# humidity_revc.net
KiCad netlist of a schematic drawn in EAGLE
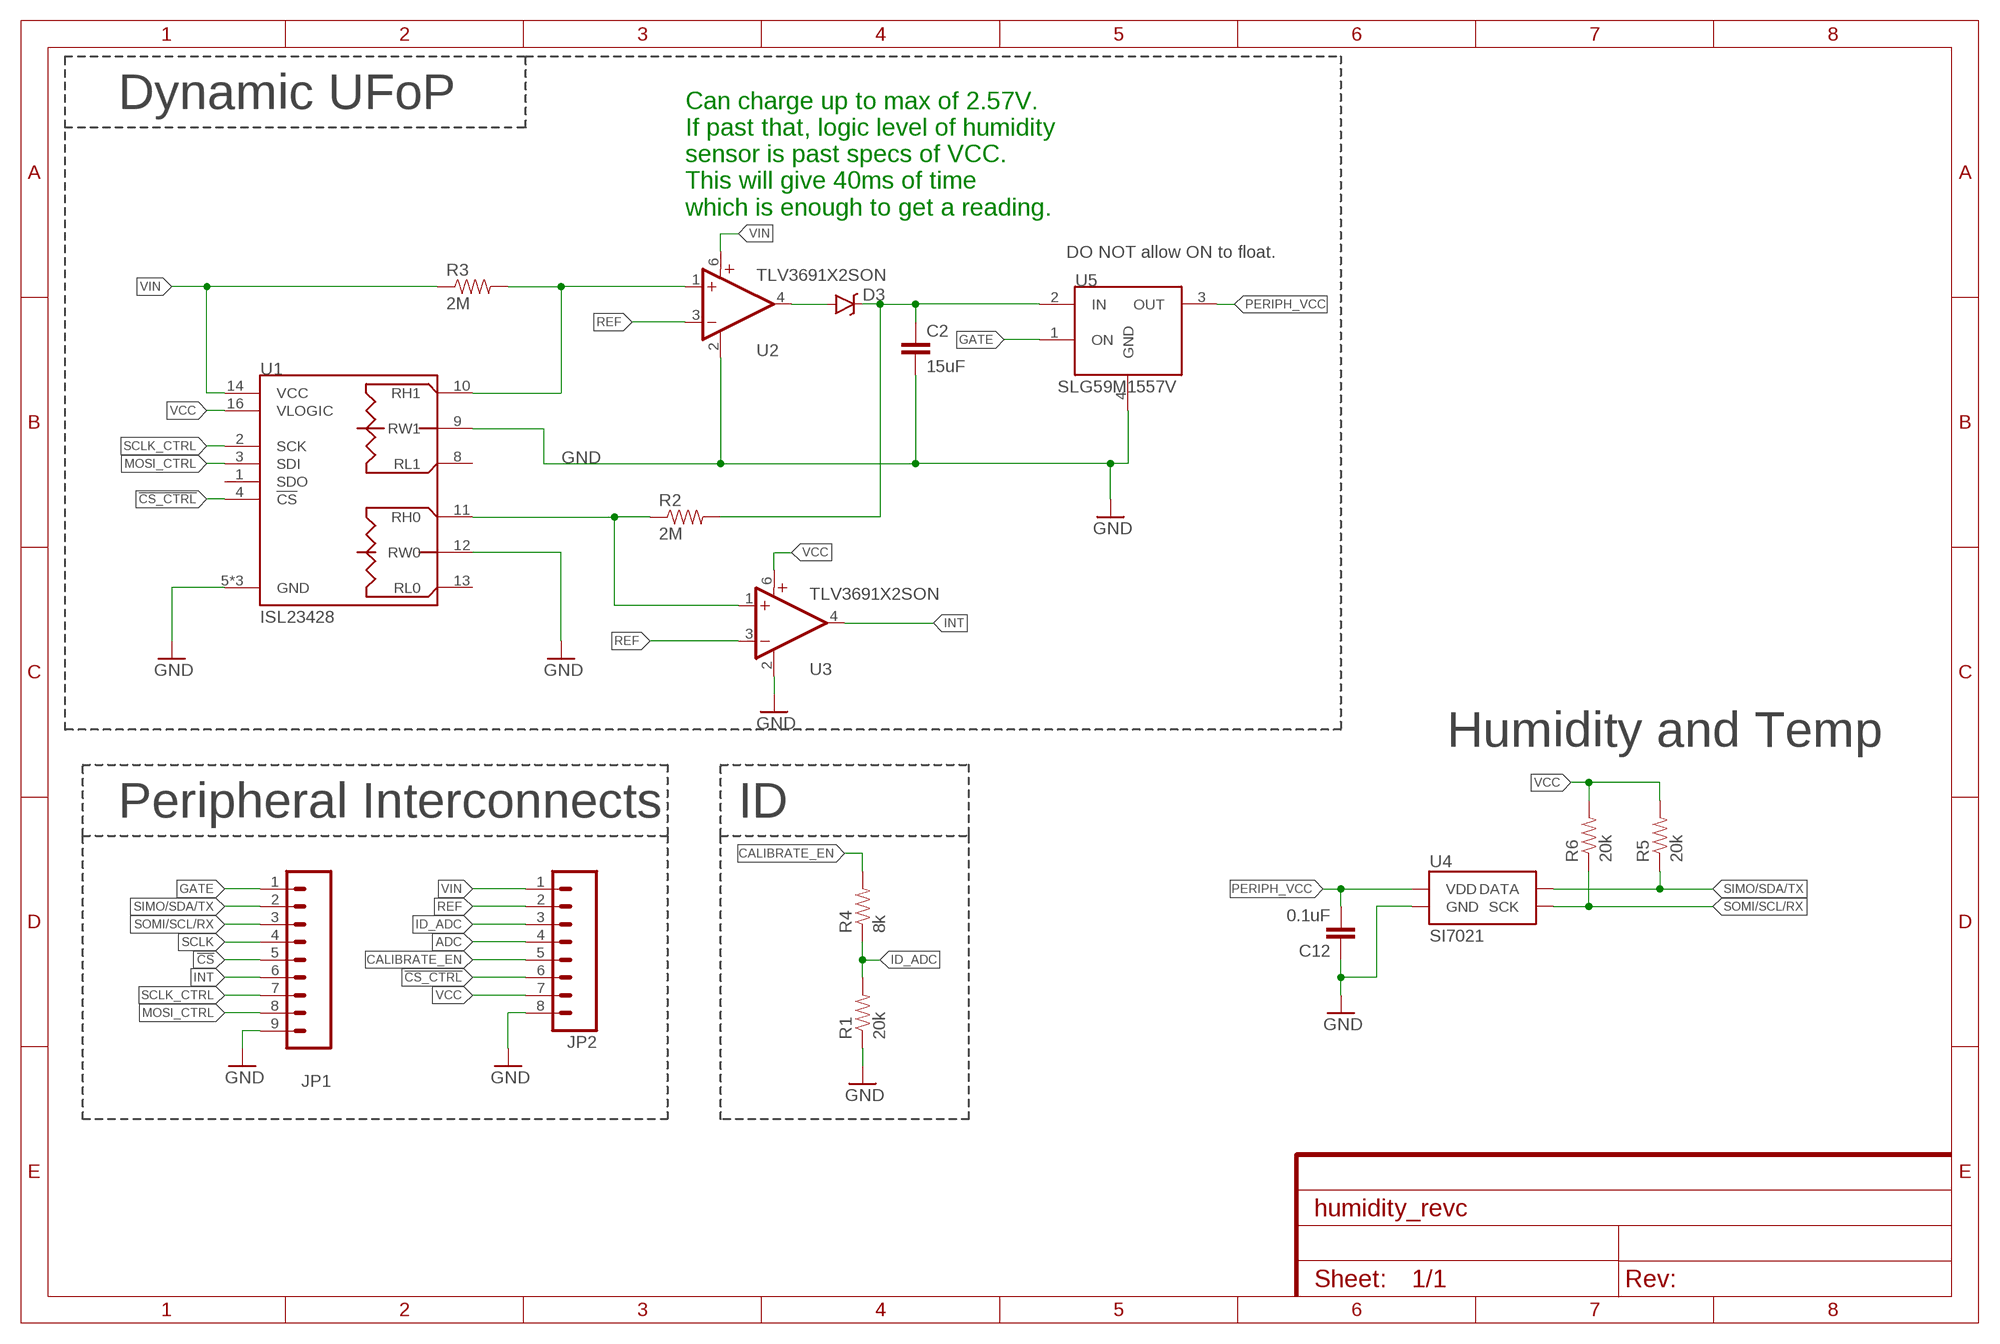
[diagram p0: schematic, sheet 1]

(export (version "E")
  (design (tool "Eeschema 10.0.6"))
  (components
    (comp (ref "C2")
      (value "15uF")
      (footprint "eagle-import:0805")
      (fields (field (name "MPN") "C2012X7S1A156M125AC"))
      (libsource (lib "eagle-import") (part "CAP0805"))
    )
    (comp (ref "C12")
      (value "0.1uF")
      (footprint "eagle-import:0402")
      (fields (field (name "MPN") "  0402YD104KAT2A"))
      (libsource (lib "eagle-import") (part "C-EU"))
    )
    (comp (ref "D3")
      (value "RB751")
      (footprint "eagle-import:SOD-523")
      (fields (field (name "MPN") "BAS40-02V-V-G-08"))
      (libsource (lib "eagle-import") (part "DIODE-SCHOTTKY-RB751"))
    )
    (comp (ref "JP1")
      (value "M091.27MM")
      (footprint "eagle-import:1X09-1.27MM")
      (fields (field (name "MANUFACTURERPARTNUMBER") "GRPB091VWVN-RC "))
      (libsource (lib "eagle-import") (part "M091.27MM"))
    )
    (comp (ref "JP2")
      (value "M081.27MM")
      (footprint "eagle-import:1X08-1.27MM")
      (fields (field (name "MANUFACTURERPARTNUMBER") "GRPB081VWVN-RC "))
      (libsource (lib "eagle-import") (part "M081.27MM"))
    )
    (comp (ref "R1")
      (value "20k")
      (footprint "eagle-import:0402")
      (fields (field (name "MPN") "ERJ-2RKF2002X"))
      (libsource (lib "eagle-import") (part "R-EU"))
    )
    (comp (ref "R2")
      (value "2M")
      (footprint "eagle-import:0402")
      (fields (field (name "MPN") "RC1005F205CS"))
      (libsource (lib "eagle-import") (part "R-EU"))
    )
    (comp (ref "R3")
      (value "2M")
      (footprint "eagle-import:0402")
      (fields (field (name "MPN") "RC1005F205CS"))
      (libsource (lib "eagle-import") (part "R-EU"))
    )
    (comp (ref "R4")
      (value "8k")
      (footprint "eagle-import:0402")
      (fields (field (name "MPN") "RC0402JR-078K2L"))
      (libsource (lib "eagle-import") (part "R-EU"))
    )
    (comp (ref "R5")
      (value "20k")
      (footprint "eagle-import:0402")
      (fields (field (name "MPN") "ERJ-2RKF2002X"))
      (libsource (lib "eagle-import") (part "R-EU"))
    )
    (comp (ref "R6")
      (value "20k")
      (footprint "eagle-import:0402")
      (fields (field (name "MPN") "ERJ-2RKF2002X"))
      (libsource (lib "eagle-import") (part "R-EU"))
    )
    (comp (ref "U1")
      (value "ISL23428")
      (footprint "eagle-import:UTQFN-16")
      (fields (field (name "MPN") "ISL23428TFRUZ-T7A"))
      (libsource (lib "eagle-import") (part "ISL23428"))
    )
    (comp (ref "U2")
      (value "TLV3691X2SON")
      (footprint "eagle-import:X2SON")
      (fields (field (name "MPN") "TLV3691IDPFR"))
      (libsource (lib "eagle-import") (part "TLV3691X2SON"))
    )
    (comp (ref "U3")
      (value "TLV3691X2SON")
      (footprint "eagle-import:X2SON")
      (fields (field (name "MPN") "TLV3691IDPFR"))
      (libsource (lib "eagle-import") (part "TLV3691X2SON"))
    )
    (comp (ref "U4")
      (value "SI7021")
      (footprint "eagle-import:SI7021")
      (fields (field (name "MPN") "SI7021-A20-GM "))
      (libsource (lib "eagle-import") (part "SI7021"))
    )
    (comp (ref "U5")
      (value "SLG59M1557V")
      (footprint "eagle-import:4STDFN")
      (fields (field (name "MPN") "SLG59M1557V "))
      (libsource (lib "eagle-import") (part "SLG59M1557V"))
    )
  )
  (nets
    (net (code "1") (name "/~{CS_CTRL}") (class "Default")
      (node (ref "JP2") (pin "6") (pinfunction "6_6") (pintype "passive"))
      (node (ref "U1") (pin "4") (pinfunction "~{CS}_4") (pintype "bidirectional"))
    )
    (net (code "2") (name "/~{CS}") (class "Default")
      (node (ref "JP1") (pin "5") (pinfunction "5_5") (pintype "passive"))
    )
    (net (code "3") (name "ADC") (class "Default")
      (node (ref "JP2") (pin "4") (pinfunction "4_4") (pintype "passive"))
    )
    (net (code "4") (name "CALIBRATE_EN") (class "Default")
      (node (ref "JP2") (pin "5") (pinfunction "5_5") (pintype "passive"))
      (node (ref "R4") (pin "2") (pinfunction "2_2") (pintype "passive"))
    )
    (net (code "5") (name "GATE") (class "Default")
      (node (ref "JP1") (pin "1") (pinfunction "1_1") (pintype "passive"))
      (node (ref "U5") (pin "1") (pinfunction "ON_1") (pintype "bidirectional"))
    )
    (net (code "6") (name "GND") (class "Default")
      (node (ref "C12") (pin "1") (pinfunction "1_1") (pintype "passive"))
      (node (ref "C2") (pin "2") (pinfunction "2_2") (pintype "passive"))
      (node (ref "JP1") (pin "9") (pinfunction "9_9") (pintype "passive"))
      (node (ref "JP2") (pin "8") (pinfunction "8_8") (pintype "passive"))
      (node (ref "R1") (pin "1") (pinfunction "1_1") (pintype "passive"))
      (node (ref "U1") (pin "12") (pinfunction "RW0_12") (pintype "bidirectional"))
      (node (ref "U1") (pin "15") (pinfunction "GND_15") (pintype "bidirectional"))
      (node (ref "U1") (pin "5") (pinfunction "GND_5") (pintype "bidirectional"))
      (node (ref "U1") (pin "6") (pinfunction "GND_6") (pintype "bidirectional"))
      (node (ref "U1") (pin "9") (pinfunction "RW1_9") (pintype "bidirectional"))
      (node (ref "U2") (pin "2") (pinfunction "GND_2") (pintype "power_in"))
      (node (ref "U3") (pin "2") (pinfunction "GND_2") (pintype "power_in"))
      (node (ref "U4") (pin "GND") (pinfunction "GND_GND") (pintype "power_in"))
      (node (ref "U5") (pin "4") (pinfunction "GND_4") (pintype "bidirectional"))
    )
    (net (code "7") (name "ID_ADC") (class "Default")
      (node (ref "JP2") (pin "3") (pinfunction "3_3") (pintype "passive"))
      (node (ref "R1") (pin "2") (pinfunction "2_2") (pintype "passive"))
      (node (ref "R4") (pin "1") (pinfunction "1_1") (pintype "passive"))
    )
    (net (code "8") (name "INT") (class "Default")
      (node (ref "JP1") (pin "6") (pinfunction "6_6") (pintype "passive"))
      (node (ref "U3") (pin "4") (pinfunction "OUT_4") (pintype "output"))
    )
    (net (code "9") (name "MOSI_CTRL") (class "Default")
      (node (ref "JP1") (pin "8") (pinfunction "8_8") (pintype "passive"))
      (node (ref "U1") (pin "3") (pinfunction "SDI_3") (pintype "bidirectional"))
    )
    (net (code "10") (name "Net-(U1-RH0)") (class "Default")
      (node (ref "R2") (pin "1") (pinfunction "1_1") (pintype "passive"))
      (node (ref "U1") (pin "11") (pinfunction "RH0_11") (pintype "bidirectional"))
      (node (ref "U3") (pin "1") (pinfunction "+IN_1") (pintype "input"))
    )
    (net (code "11") (name "Net-(U1-RH1)") (class "Default")
      (node (ref "R3") (pin "2") (pinfunction "2_2") (pintype "passive"))
      (node (ref "U1") (pin "10") (pinfunction "RH1_10") (pintype "bidirectional"))
      (node (ref "U2") (pin "1") (pinfunction "+IN_1") (pintype "input"))
    )
    (net (code "12") (name "Net-(U2-OUT)") (class "Default")
      (node (ref "D3") (pin "A") (pinfunction "A_A") (pintype "passive"))
      (node (ref "U2") (pin "4") (pinfunction "OUT_4") (pintype "output"))
    )
    (net (code "13") (name "Net-(U5-IN)") (class "Default")
      (node (ref "C2") (pin "1") (pinfunction "1_1") (pintype "passive"))
      (node (ref "D3") (pin "C") (pinfunction "C_C") (pintype "passive"))
      (node (ref "R2") (pin "2") (pinfunction "2_2") (pintype "passive"))
      (node (ref "U5") (pin "2") (pinfunction "IN_2") (pintype "bidirectional"))
    )
    (net (code "14") (name "PERIPH_VCC") (class "Default")
      (node (ref "C12") (pin "2") (pinfunction "2_2") (pintype "passive"))
      (node (ref "U4") (pin "VDD") (pinfunction "VDD_VDD") (pintype "power_in"))
      (node (ref "U5") (pin "3") (pinfunction "OUT_3") (pintype "bidirectional"))
    )
    (net (code "15") (name "REF") (class "Default")
      (node (ref "JP2") (pin "2") (pinfunction "2_2") (pintype "passive"))
      (node (ref "U2") (pin "3") (pinfunction "-IN_3") (pintype "input"))
      (node (ref "U3") (pin "3") (pinfunction "-IN_3") (pintype "input"))
    )
    (net (code "16") (name "SCLK") (class "Default")
      (node (ref "JP1") (pin "4") (pinfunction "4_4") (pintype "passive"))
    )
    (net (code "17") (name "SCLK_CTRL") (class "Default")
      (node (ref "JP1") (pin "7") (pinfunction "7_7") (pintype "passive"))
      (node (ref "U1") (pin "2") (pinfunction "SCK_2") (pintype "bidirectional"))
    )
    (net (code "18") (name "SIMO{slash}SDA{slash}TX") (class "Default")
      (node (ref "JP1") (pin "2") (pinfunction "2_2") (pintype "passive"))
      (node (ref "R5") (pin "1") (pinfunction "1_1") (pintype "passive"))
      (node (ref "U4") (pin "DATA") (pinfunction "DATA_DATA") (pintype "bidirectional"))
    )
    (net (code "19") (name "SOMI{slash}SCL{slash}RX") (class "Default")
      (node (ref "JP1") (pin "3") (pinfunction "3_3") (pintype "passive"))
      (node (ref "R6") (pin "1") (pinfunction "1_1") (pintype "passive"))
      (node (ref "U4") (pin "SCK") (pinfunction "SCK_SCK") (pintype "input"))
    )
    (net (code "20") (name "VCC") (class "Default")
      (node (ref "JP2") (pin "7") (pinfunction "7_7") (pintype "passive"))
      (node (ref "R5") (pin "2") (pinfunction "2_2") (pintype "passive"))
      (node (ref "R6") (pin "2") (pinfunction "2_2") (pintype "passive"))
      (node (ref "U1") (pin "16") (pinfunction "VLOGIC_16") (pintype "bidirectional"))
      (node (ref "U3") (pin "6") (pinfunction "V+_6") (pintype "power_in"))
    )
    (net (code "21") (name "VIN") (class "Default")
      (node (ref "JP2") (pin "1") (pinfunction "1_1") (pintype "passive"))
      (node (ref "R3") (pin "1") (pinfunction "1_1") (pintype "passive"))
      (node (ref "U1") (pin "14") (pinfunction "VCC_14") (pintype "bidirectional"))
      (node (ref "U2") (pin "6") (pinfunction "V+_6") (pintype "power_in"))
    )
    (net (code "22") (name "unconnected-(U1-RL0-Pad13)") (class "Default")
      (node (ref "U1") (pin "13") (pinfunction "RL0_13") (pintype "bidirectional"))
    )
    (net (code "23") (name "unconnected-(U1-RL1-Pad8)") (class "Default")
      (node (ref "U1") (pin "8") (pinfunction "RL1_8") (pintype "bidirectional"))
    )
    (net (code "24") (name "unconnected-(U1-SDO-Pad1)") (class "Default")
      (node (ref "U1") (pin "1") (pinfunction "SDO_1") (pintype "bidirectional"))
    )
  )
)
